# sensors_and_IOs.net
KiCad netlist of a schematic drawn in Altium Designer
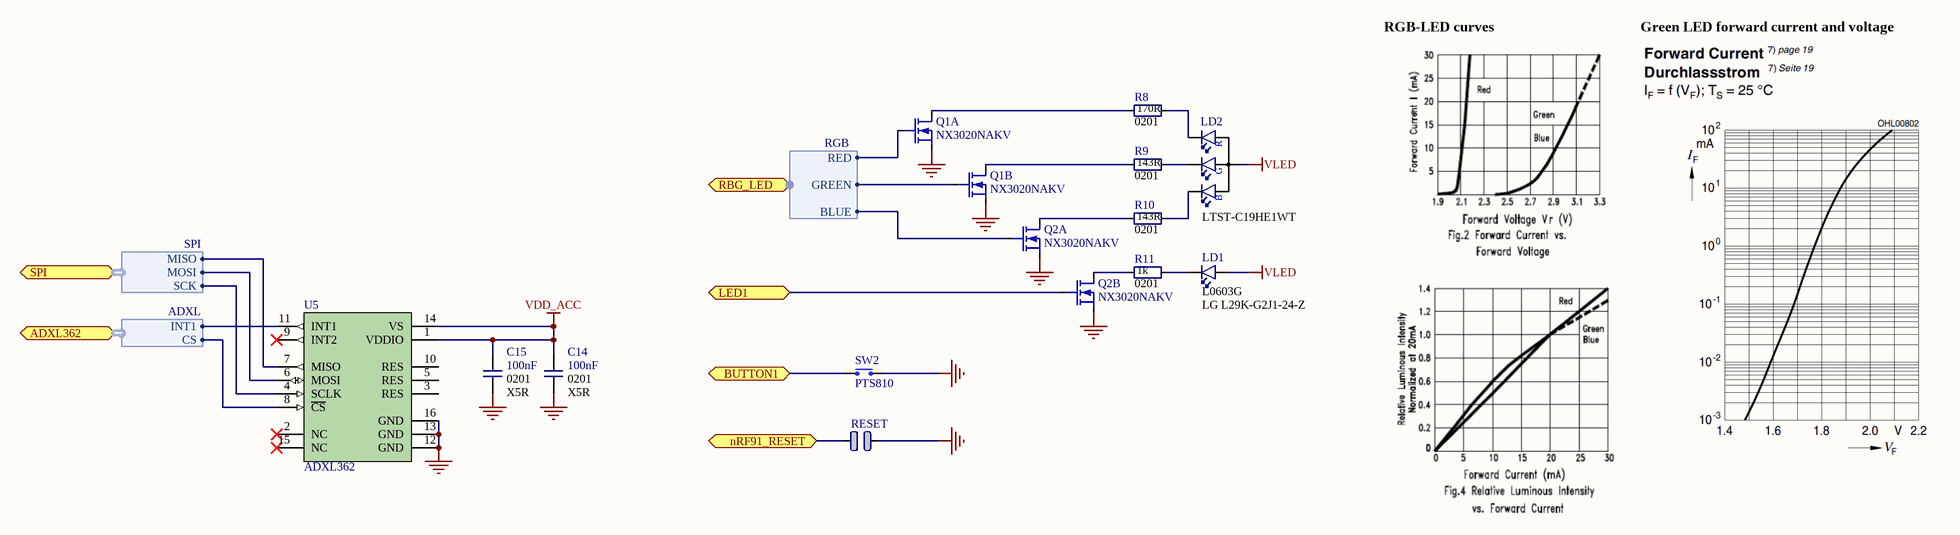
[diagram p0: _sensors_and_IOs.SchDoc]

(export (version "E")
  (design (tool "Eeschema 10.0.6"))
  (components
    (comp (ref "C14")
      (value "100nF")
      (footprint "CAPC0603X03L_C")
      (description "Capacitor, X5R, ±10%, 10V")
      (fields
        (field (name "FOOTPRINT DOC") "0201")
        (field (name "TEMPCOEFF") "X5R")
        (field (name "PUBLISHER") "Nordic Semiconductor")
      )
      (libsource (lib "_components") (part "CAP{colon}0201"))
    )
    (comp (ref "C15")
      (value "100nF")
      (footprint "CAPC0603X03L_C")
      (description "Capacitor, X5R, ±10%, 10V")
      (fields
        (field (name "FOOTPRINT DOC") "0201")
        (field (name "TEMPCOEFF") "X5R")
        (field (name "PUBLISHER") "Nordic Semiconductor")
      )
      (libsource (lib "_components") (part "CAP{colon}0201"))
    )
    (comp (ref "LD1")
      (value "L0603G")
      (footprint "LED_0603_G")
      (description "LED, Green, 0603, 570nm, Vf=1.7V, 2.24..5.6mcd, - 40 to +100°C")
      (fields
        (field (name "PART NUMBER") "LG L29K Smartled Green")
        (field (name "MANUFACTURER") "Osram")
        (field (name "MANUFACTURER PART NUMBER") "LG L29K-G2J1-24-Z")
        (field (name "PUBLISHER") "Nordic Semiconductor")
      )
      (libsource (lib "_components") (part "D{colon}LED"))
    )
    (comp (ref "LD2")
      (value "LED RGB")
      (footprint "LED_RGB_0606")
      (description "RGB LED 1.60 mm x 1.60 mm SMD")
      (fields
        (field (name "PART NUMBER") "LTST-C19HE1WT")
        (field (name "MANUFACTURER") "Lite-On Inc")
        (field (name "MANUFACTURER PART NUMBER") "LTST-C19HE1WT")
        (field (name "PUBLISHER") "Nordic Semiconductor")
      )
      (libsource (lib "_components") (part "D{colon}LED_RGB"))
    )
    (comp (ref "Q1")
      (value "NX3020NAKV")
      (footprint "NX3020NAKV")
      (description "MOSFET 2N-CH 30V 0.2A SOT666")
      (fields
        (field (name "MANUFACTURER") "Nexperia")
        (field (name "MANUFACTURER PART NUMBER") "NX3020NAKV,115")
        (field (name "PUBLISHER") "Nordic Semiconductor")
      )
      (libsource (lib "_components") (part "T{colon}FET-N-DUAL"))
    )
    (comp (ref "Q2")
      (value "NX3020NAKV")
      (footprint "NX3020NAKV")
      (description "MOSFET 2N-CH 30V 0.2A SOT666")
      (fields
        (field (name "MANUFACTURER") "Nexperia")
        (field (name "MANUFACTURER PART NUMBER") "NX3020NAKV,115")
        (field (name "PUBLISHER") "Nordic Semiconductor")
      )
      (libsource (lib "_components") (part "T{colon}FET-N-DUAL"))
    )
    (comp (ref "R8")
      (value "170R")
      (footprint "RESC0603X03L_C")
      (fields (field (name "FOOTPRINT DOC") "0201") (field (name "PUBLISHER") "Nordic Semiconductor"))
      (libsource (lib "_components") (part "RES{colon}0201"))
    )
    (comp (ref "R9")
      (value "143R")
      (footprint "RESC0603X03L_C")
      (fields (field (name "FOOTPRINT DOC") "0201") (field (name "PUBLISHER") "Nordic Semiconductor"))
      (libsource (lib "_components") (part "RES{colon}0201"))
    )
    (comp (ref "R10")
      (value "143R")
      (footprint "RESC0603X03L_C")
      (fields (field (name "FOOTPRINT DOC") "0201") (field (name "PUBLISHER") "Nordic Semiconductor"))
      (libsource (lib "_components") (part "RES{colon}0201"))
    )
    (comp (ref "R11")
      (value "1k")
      (footprint "RESC0603X03L_C")
      (fields (field (name "FOOTPRINT DOC") "0201") (field (name "PUBLISHER") "Nordic Semiconductor"))
      (libsource (lib "_components") (part "RES{colon}0201"))
    )
    (comp (ref "RESET")
      (value "Solderbridge")
      (footprint "Solderbridge")
      (fields (field (name "PUBLISHER") "Nordic Semiconductor"))
      (libsource (lib "_components") (part "SOLDERBRIDGE"))
    )
    (comp (ref "SW2")
      (value "PTS810")
      (footprint "BTN_PTS810")
      (description "SWITCH TACTILE SPST-NO 0.05A 16V")
      (fields
        (field (name "MANUFACTURER PART NUMBER") "PTS810 SJM 250 SMTR LFS")
        (field (name "MANUFACTURER") "C&K")
      )
      (libsource (lib "_components") (part "BUTTON"))
    )
    (comp (ref "U5")
      (value "ADXL362")
      (footprint "LGA50P322X300X114-16N")
      (description "Micropower, 3-Axis, ±2 g/±4 g/±8 g Digital Output MEMS Accelerometer")
      (fields
        (field (name "MANUFACTURER") "Analog Devices")
        (field (name "PUBLISHER") "Nordic Semiconductor")
      )
      (libsource (lib "_components") (part "ADXL362"))
    )
  )
  (nets
    (net (code "4") (name "/BLUE") (class "Default")
      (node (ref "Q2") (pin "2") (pinfunction "G1_2") (pintype "passive"))
    )
    (net (code "5") (name "/BUTTON1") (class "Default")
      (node (ref "SW2") (pin "2") (pinfunction "2_2") (pintype "passive"))
    )
    (net (code "6") (name "/CS") (class "Default")
      (node (ref "U5") (pin "8") (pinfunction "~{CS}_8") (pintype "input"))
    )
    (net (code "7") (name "/GREEN") (class "Default")
      (node (ref "Q1") (pin "5") (pinfunction "G2_5") (pintype "passive"))
    )
    (net (code "8") (name "/INT1") (class "Default")
      (node (ref "U5") (pin "11") (pinfunction "INT1_11") (pintype "output"))
    )
    (net (code "9") (name "/LED1") (class "Default")
      (node (ref "Q2") (pin "5") (pinfunction "G2_5") (pintype "passive"))
    )
    (net (code "10") (name "/MISO") (class "Default")
      (node (ref "U5") (pin "7") (pinfunction "MISO_7") (pintype "output"))
    )
    (net (code "11") (name "/MOSI") (class "Default")
      (node (ref "U5") (pin "6") (pinfunction "MOSI_6") (pintype "bidirectional"))
    )
    (net (code "12") (name "/RED") (class "Default")
      (node (ref "Q1") (pin "2") (pinfunction "G1_2") (pintype "passive"))
    )
    (net (code "13") (name "/SCK") (class "Default")
      (node (ref "U5") (pin "4") (pinfunction "SCLK_4") (pintype "input"))
    )
    (net (code "14") (name "/nRF91_RESET") (class "Default")
      (node (ref "RESET") (pin "2") (pinfunction "1_2") (pintype "passive"))
    )
    (net (code "18") (name "GND") (class "Default")
      (node (ref "C14") (pin "2") (pinfunction "2_2") (pintype "passive"))
      (node (ref "C15") (pin "2") (pinfunction "2_2") (pintype "passive"))
      (node (ref "Q1") (pin "1") (pinfunction "S1_1") (pintype "passive"))
      (node (ref "Q1") (pin "4") (pinfunction "S2_4") (pintype "passive"))
      (node (ref "Q2") (pin "1") (pinfunction "S1_1") (pintype "passive"))
      (node (ref "Q2") (pin "4") (pinfunction "S2_4") (pintype "passive"))
      (node (ref "RESET") (pin "1") (pinfunction "0_1") (pintype "passive"))
      (node (ref "SW2") (pin "1") (pinfunction "1_1") (pintype "passive"))
      (node (ref "U5") (pin "12") (pinfunction "GND_12") (pintype "power_in"))
      (node (ref "U5") (pin "13") (pinfunction "GND_13") (pintype "power_in"))
      (node (ref "U5") (pin "16") (pinfunction "GND_16") (pintype "power_in"))
    )
    (net (code "19") (name "Net-(LD1-C)") (class "Default")
      (node (ref "LD1") (pin "1") (pinfunction "C_1") (pintype "passive"))
      (node (ref "R11") (pin "2") (pinfunction "2_2") (pintype "passive"))
    )
    (net (code "20") (name "Net-(LD2-C_BLUE)") (class "Default")
      (node (ref "LD2") (pin "3") (pinfunction "C_BLUE_3") (pintype "passive"))
      (node (ref "R10") (pin "2") (pinfunction "2_2") (pintype "passive"))
    )
    (net (code "21") (name "Net-(LD2-C_GREEN)") (class "Default")
      (node (ref "LD2") (pin "2") (pinfunction "C_GREEN_2") (pintype "passive"))
      (node (ref "R9") (pin "2") (pinfunction "2_2") (pintype "passive"))
    )
    (net (code "22") (name "Net-(LD2-C_RED)") (class "Default")
      (node (ref "LD2") (pin "1") (pinfunction "C_RED_1") (pintype "passive"))
      (node (ref "R8") (pin "2") (pinfunction "2_2") (pintype "passive"))
    )
    (net (code "23") (name "Net-(Q1A-D1)") (class "Default")
      (node (ref "Q1") (pin "6") (pinfunction "D1_6") (pintype "passive"))
      (node (ref "R8") (pin "1") (pinfunction "1_1") (pintype "passive"))
    )
    (net (code "24") (name "Net-(Q1B-D2)") (class "Default")
      (node (ref "Q1") (pin "3") (pinfunction "D2_3") (pintype "passive"))
      (node (ref "R9") (pin "1") (pinfunction "1_1") (pintype "passive"))
    )
    (net (code "25") (name "Net-(Q2A-D1)") (class "Default")
      (node (ref "Q2") (pin "6") (pinfunction "D1_6") (pintype "passive"))
      (node (ref "R10") (pin "1") (pinfunction "1_1") (pintype "passive"))
    )
    (net (code "26") (name "Net-(Q2B-D2)") (class "Default")
      (node (ref "Q2") (pin "3") (pinfunction "D2_3") (pintype "passive"))
      (node (ref "R11") (pin "1") (pinfunction "1_1") (pintype "passive"))
    )
    (net (code "27") (name "VDD_ACC") (class "Default")
      (node (ref "C14") (pin "1") (pinfunction "1_1") (pintype "passive"))
      (node (ref "C15") (pin "1") (pinfunction "1_1") (pintype "passive"))
      (node (ref "U5") (pin "1") (pinfunction "VDDIO_1") (pintype "power_in"))
      (node (ref "U5") (pin "14") (pinfunction "VS_14") (pintype "power_in"))
    )
    (net (code "28") (name "VLED") (class "Default")
      (node (ref "LD1") (pin "2") (pinfunction "A_2") (pintype "passive"))
      (node (ref "LD2") (pin "4") (pinfunction "A_4") (pintype "passive"))
    )
    (net (code "29") (name "unconnected-(U5-INT2-Pad9)") (class "Default")
      (node (ref "U5") (pin "9") (pinfunction "INT2_9") (pintype "output+no_connect"))
    )
    (net (code "30") (name "unconnected-(U5-NC-Pad2)") (class "Default")
      (node (ref "U5") (pin "2") (pinfunction "NC_2") (pintype "passive+no_connect"))
    )
    (net (code "31") (name "unconnected-(U5-NC-Pad15)") (class "Default")
      (node (ref "U5") (pin "15") (pinfunction "NC_15") (pintype "passive+no_connect"))
    )
    (net (code "32") (name "unconnected-(U5-RES-Pad3)") (class "Default")
      (node (ref "U5") (pin "3") (pinfunction "RES_3") (pintype "passive"))
    )
    (net (code "33") (name "unconnected-(U5-RES-Pad5)") (class "Default")
      (node (ref "U5") (pin "5") (pinfunction "RES_5") (pintype "passive"))
    )
    (net (code "34") (name "unconnected-(U5-RES-Pad10)") (class "Default")
      (node (ref "U5") (pin "10") (pinfunction "RES_10") (pintype "passive"))
    )
  )
)
